# MIXR_Power_-_Battery_Charging.net
KiCad netlist of a schematic drawn in Altium Designer
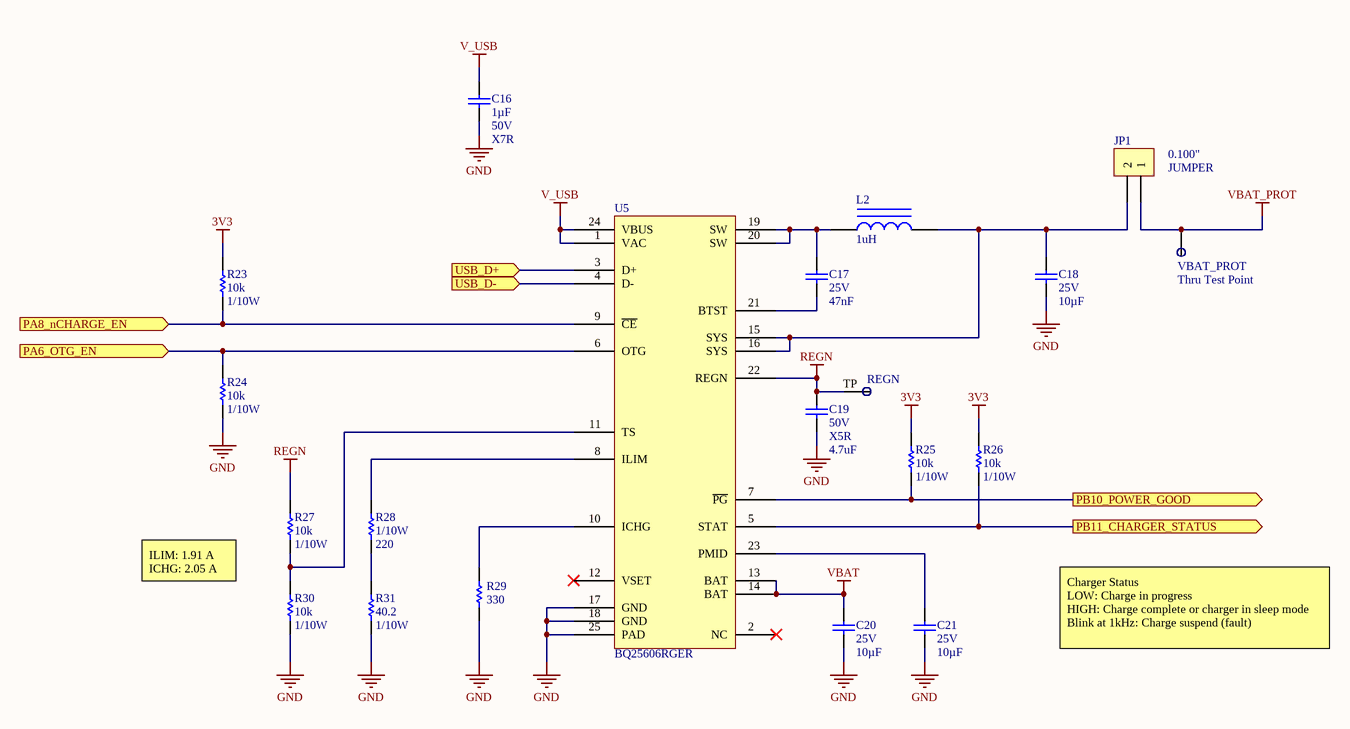
[diagram p0: MIXR Power - Battery Charging.SchDoc]

(export (version "E")
  (design (tool "Eeschema 10.0.6"))
  (components
    (comp (ref "C16")
      (value "CAP CER 1UF 50V 10% X7R 0603")
      (footprint "CAP, 0603")
      (description "1µF ±10% 50V Ceramic Capacitor X7R 0603 (1608 Metric)")
      (fields
        (field (name "TOLERANCE") "±10%")
        (field (name "CAPACITANCE") "1µF")
        (field (name "VOLTAGE") "50V")
        (field (name "TEMPERATURE COEFFICIENT") "X7R")
      )
      (libsource (lib "Schematic Diagrams") (part "CAP CER 1UF 50V 10% X7R 0603"))
    )
    (comp (ref "C17")
      (value "CAP CER 0.047UF 10% 25V X7R 0603")
      (footprint "CAP, 0603")
      (description "0.047µF ±10% 25V Ceramic Capacitor X7R 0603 (1608 Metric)")
      (fields
        (field (name "MANUFACTURER") "KEMET")
        (field (name "TOLERANCE") "10%")
        (field (name "VOLTAGE") "25V")
        (field (name "CAPACITANCE") "47nF")
      )
      (libsource (lib "Schematic Diagrams") (part "CAP CER 0.047UF 10% 25V X7R 0603"))
    )
    (comp (ref "C18")
      (value "CAP CER 10uF 25V 10% X5R 0805")
      (footprint "CAP, 0805")
      (description "10µF ±10% 25V Ceramic Capacitor X5R 0805 (2012 Metric)")
      (fields
        (field (name "MANUFACTURER") "Murata Electronics North America")
        (field (name "MANUFACTURER PART NUMBER") "GRM21BR61E106KA73L")
        (field (name "VOLTAGE - RATED") "25V")
        (field (name "CAPACITANCE") "10µF")
      )
      (libsource (lib "Schematic Diagrams") (part "CAP CER 10uF 25V 10% X5R 0805"))
    )
    (comp (ref "C19")
      (value "4.7uF")
      (footprint "CAP, 0805")
      (description "4.7µF ±20% 50V Ceramic Capacitor X5R 0805 (2012 Metric)")
      (fields
        (field (name "TOLERANCE") "±20%")
        (field (name "VOLTAGE - RATED") "50V")
        (field (name "TEMPERATURE COEFFICIENT") "X5R")
        (field (name "Comment") "CAP CER 4.7UF 50V 10% X5R 0805")
      )
      (libsource (lib "Schematic Diagrams") (part "CAP CER 4.7UF 50V 10% X5R 0805"))
    )
    (comp (ref "C20")
      (value "CAP CER 10uF 25V 10% X5R 0805")
      (footprint "CAP, 0805")
      (description "10µF ±10% 25V Ceramic Capacitor X5R 0805 (2012 Metric)")
      (fields
        (field (name "MANUFACTURER") "Murata Electronics North America")
        (field (name "MANUFACTURER PART NUMBER") "GRM21BR61E106KA73L")
        (field (name "VOLTAGE - RATED") "25V")
        (field (name "CAPACITANCE") "10µF")
      )
      (libsource (lib "Schematic Diagrams") (part "CAP CER 10uF 25V 10% X5R 0805"))
    )
    (comp (ref "C21")
      (value "CAP CER 10uF 25V 10% X5R 0805")
      (footprint "CAP, 0805")
      (description "10µF ±10% 25V Ceramic Capacitor X5R 0805 (2012 Metric)")
      (fields
        (field (name "MANUFACTURER") "Murata Electronics North America")
        (field (name "MANUFACTURER PART NUMBER") "GRM21BR61E106KA73L")
        (field (name "VOLTAGE - RATED") "25V")
        (field (name "CAPACITANCE") "10µF")
      )
      (libsource (lib "Schematic Diagrams") (part "CAP CER 10uF 25V 10% X5R 0805"))
    )
    (comp (ref "JP1")
      (value "JUMPER")
      (footprint "CONN, 2POS JUMPER 0.1\"")
      (description "2 Positions Header Connector Through Hole Gold")
      (fields
        (field (name "MANUFACTURER") "Omron Electronics Inc-EMC Div")
        (field (name "MANUFACTURER PART NUMBER") "XG8T-0231")
        (field (name "ROW SPACING - MATING") "0.100\"")
        (field (name "TYPE") "JUMPER")
      )
      (libsource (lib "Schematic Diagrams") (part "CONN 2POS JUMPER 0.1{dblquote}"))
    )
    (comp (ref "L2")
      (value "IND 1uH 3.8A 25 MOHM SMD")
      (footprint "IND 1uH 3.8A 25 MOHM SMD")
      (description "1µH Shielded Inductor 3.8A 25mOhm Max Nonstandard")
      (fields
        (field (name "MANUFACTURER") "Vishay Dale")
        (field (name "TOLERANCE") "20%")
        (field (name "INDUCTANCE") "1uH")
      )
      (libsource (lib "Schematic Diagrams") (part "IND 1uH 3.8A 25 MOHM SMD"))
    )
    (comp (ref "R23")
      (value "RES 10K OHM 1% 1/10W 0603")
      (footprint "RES, 0603")
      (description "RES SMD 10K OHM 1% 1/10W 0603")
      (fields
        (field (name "TOLERANCE") "±1%")
        (field (name "RESISTANCE") "10k")
        (field (name "POWER") "1/10W")
      )
      (libsource (lib "Schematic Diagrams") (part "RES 10K OHM 1% 1/10W 0603"))
    )
    (comp (ref "R24")
      (value "RES 10K OHM 1% 1/10W 0603")
      (footprint "RES, 0603")
      (description "RES SMD 10K OHM 1% 1/10W 0603")
      (fields
        (field (name "TOLERANCE") "±1%")
        (field (name "RESISTANCE") "10k")
        (field (name "POWER") "1/10W")
      )
      (libsource (lib "Schematic Diagrams") (part "RES 10K OHM 1% 1/10W 0603"))
    )
    (comp (ref "R25")
      (value "RES 10K OHM 1% 1/10W 0603")
      (footprint "RES, 0603")
      (description "RES SMD 10K OHM 1% 1/10W 0603")
      (fields
        (field (name "TOLERANCE") "±1%")
        (field (name "RESISTANCE") "10k")
        (field (name "POWER") "1/10W")
      )
      (libsource (lib "Schematic Diagrams") (part "RES 10K OHM 1% 1/10W 0603"))
    )
    (comp (ref "R26")
      (value "RES 10K OHM 1% 1/10W 0603")
      (footprint "RES, 0603")
      (description "RES SMD 10K OHM 1% 1/10W 0603")
      (fields
        (field (name "TOLERANCE") "±1%")
        (field (name "RESISTANCE") "10k")
        (field (name "POWER") "1/10W")
      )
      (libsource (lib "Schematic Diagrams") (part "RES 10K OHM 1% 1/10W 0603"))
    )
    (comp (ref "R27")
      (value "RES 10K OHM 1% 1/10W 0603")
      (footprint "RES, 0603")
      (description "RES SMD 10K OHM 1% 1/10W 0603")
      (fields
        (field (name "TOLERANCE") "±1%")
        (field (name "RESISTANCE") "10k")
        (field (name "POWER") "1/10W")
      )
      (libsource (lib "Schematic Diagrams") (part "RES 10K OHM 1% 1/10W 0603"))
    )
    (comp (ref "R28")
      (value "RES 220 OHM 1% 1/10W 0603")
      (footprint "RES, 0603")
      (description "220 Ohms ±1% 0.1W, 1/10W Chip Resistor 0603 (1608 Metric) Moisture Resistant Thick Film")
      (fields
        (field (name "MANUFACTURER") "Yageo")
        (field (name "MANUFACTURER PART NUMBER") "RC0603FR-07220RL")
        (field (name "POWER (WATTS)") "1/10W")
        (field (name "RESISTANCE") "220")
      )
      (libsource (lib "Schematic Diagrams") (part "RES 220 OHM 1% 1/10W 0603"))
    )
    (comp (ref "R29")
      (value "330")
      (footprint "RES, 0603")
      (fields
        (field (name "MANUFACTURER") "TE Connectivity")
        (field (name "MANUFACTURER PART NUMBER") "CRGCQ0603F330R")
        (field (name "Comment") "RES 330 OHM 1% 1/10W 0603")
      )
      (libsource (lib "Schematic Diagrams") (part "RES 330 OHM 1% 1/10W 0603"))
    )
    (comp (ref "R30")
      (value "RES 10K OHM 1% 1/10W 0603")
      (footprint "RES, 0603")
      (description "RES SMD 10K OHM 1% 1/10W 0603")
      (fields
        (field (name "TOLERANCE") "±1%")
        (field (name "RESISTANCE") "10k")
        (field (name "POWER") "1/10W")
      )
      (libsource (lib "Schematic Diagrams") (part "RES 10K OHM 1% 1/10W 0603"))
    )
    (comp (ref "R31")
      (value "RES 40.2 OHM 0.5% 1/10W 0603")
      (footprint "RES, 0603")
      (description "RES SMD 40.2 OHM 0.5% 1/10W 0603")
      (fields
        (field (name "TOLERANCE") "±0.5%")
        (field (name "RESISTANCE") "40.2")
        (field (name "POWER") "1/10W")
      )
      (libsource (lib "Schematic Diagrams") (part "RES 40.2 OHM 0.5% 1/10W 0603"))
    )
    (comp (ref "REGN")
      (value "Test Point")
      (footprint "Test Point")
      (libsource (lib "Schematic Diagrams") (part "Test Point"))
    )
    (comp (ref "U5")
      (value "IC BATT CHG LI-ION 1 CELL 24-VQFN")
      (footprint "IC BATT CHG LI-ION 1 CELL 24-VQFN")
      (description "Charger IC Lithium Ion/Polymer 24-VQFN (4x4)")
      (fields
        (field (name "MANUFACTURER") "Texas Instruments")
        (field (name "MANUFACTURER PART NUMBER") "BQ25606RGER")
      )
      (libsource (lib "Schematic Diagrams") (part "IC BATT CHG LI-ION 1 CELL 24-VQFN"))
    )
    (comp (ref "VBAT_PROT")
      (value "Thru Test Point")
      (footprint "Thru Test Point")
      (libsource (lib "Schematic Diagrams") (part "Thru Test Point"))
    )
  )
  (nets
    (net (code "1") (name "/PA6_OTG_EN") (class "Default")
      (node (ref "R24") (pin "1") (pinfunction "1_1") (pintype "passive"))
      (node (ref "U5") (pin "6") (pinfunction "OTG_6") (pintype "passive"))
    )
    (net (code "2") (name "/PA8_nCHARGE_EN") (class "Default")
      (node (ref "R23") (pin "2") (pinfunction "2_2") (pintype "passive"))
      (node (ref "U5") (pin "9") (pinfunction "~{CE}_9") (pintype "passive"))
    )
    (net (code "3") (name "/PB10_POWER_GOOD") (class "Default")
      (node (ref "R25") (pin "2") (pinfunction "2_2") (pintype "passive"))
      (node (ref "U5") (pin "7") (pinfunction "~{PG}_7") (pintype "passive"))
    )
    (net (code "4") (name "/PB11_CHARGER_STATUS") (class "Default")
      (node (ref "R26") (pin "2") (pinfunction "2_2") (pintype "passive"))
      (node (ref "U5") (pin "5") (pinfunction "STAT_5") (pintype "passive"))
    )
    (net (code "5") (name "/USB_D+") (class "Default")
      (node (ref "U5") (pin "3") (pinfunction "D+_3") (pintype "passive"))
    )
    (net (code "6") (name "/USB_D-") (class "Default")
      (node (ref "U5") (pin "4") (pinfunction "D-_4") (pintype "passive"))
    )
    (net (code "7") (name "3V3") (class "Default")
      (node (ref "R23") (pin "1") (pinfunction "1_1") (pintype "passive"))
      (node (ref "R25") (pin "1") (pinfunction "1_1") (pintype "passive"))
      (node (ref "R26") (pin "1") (pinfunction "1_1") (pintype "passive"))
    )
    (net (code "8") (name "GND") (class "Default")
      (node (ref "C16") (pin "2") (pinfunction "2_2") (pintype "passive"))
      (node (ref "C18") (pin "2") (pinfunction "2_2") (pintype "passive"))
      (node (ref "C19") (pin "2") (pinfunction "2_2") (pintype "passive"))
      (node (ref "C20") (pin "2") (pinfunction "2_2") (pintype "passive"))
      (node (ref "C21") (pin "2") (pinfunction "2_2") (pintype "passive"))
      (node (ref "R24") (pin "2") (pinfunction "2_2") (pintype "passive"))
      (node (ref "R29") (pin "2") (pinfunction "2_2") (pintype "passive"))
      (node (ref "R30") (pin "2") (pinfunction "2_2") (pintype "passive"))
      (node (ref "R31") (pin "2") (pinfunction "2_2") (pintype "passive"))
      (node (ref "U5") (pin "17") (pinfunction "GND_17") (pintype "passive"))
      (node (ref "U5") (pin "18") (pinfunction "GND_18") (pintype "passive"))
      (node (ref "U5") (pin "25") (pinfunction "PAD_25") (pintype "passive"))
    )
    (net (code "9") (name "Net-(C17-Pad1)") (class "Default")
      (node (ref "C17") (pin "1") (pinfunction "1_1") (pintype "passive"))
      (node (ref "L2") (pin "1") (pinfunction "1_1") (pintype "passive"))
      (node (ref "U5") (pin "19") (pinfunction "SW_19") (pintype "passive"))
      (node (ref "U5") (pin "20") (pinfunction "SW_20") (pintype "passive"))
    )
    (net (code "10") (name "Net-(C18-Pad1)") (class "Default")
      (node (ref "C18") (pin "1") (pinfunction "1_1") (pintype "passive"))
      (node (ref "JP1") (pin "2") (pinfunction "2_2") (pintype "passive"))
      (node (ref "L2") (pin "2") (pinfunction "2_2") (pintype "passive"))
      (node (ref "U5") (pin "15") (pinfunction "SYS_15") (pintype "passive"))
      (node (ref "U5") (pin "16") (pinfunction "SYS_16") (pintype "passive"))
    )
    (net (code "11") (name "Net-(R28-Pad2)") (class "Default")
      (node (ref "R28") (pin "2") (pinfunction "2_2") (pintype "passive"))
      (node (ref "R31") (pin "1") (pinfunction "1_1") (pintype "passive"))
    )
    (net (code "12") (name "Net-(U5-BTST)") (class "Default")
      (node (ref "C17") (pin "2") (pinfunction "2_2") (pintype "passive"))
      (node (ref "U5") (pin "21") (pinfunction "BTST_21") (pintype "passive"))
    )
    (net (code "13") (name "Net-(U5-ICHG)") (class "Default")
      (node (ref "R29") (pin "1") (pinfunction "1_1") (pintype "passive"))
      (node (ref "U5") (pin "10") (pinfunction "ICHG_10") (pintype "passive"))
    )
    (net (code "14") (name "Net-(U5-ILIM)") (class "Default")
      (node (ref "R28") (pin "1") (pinfunction "1_1") (pintype "passive"))
      (node (ref "U5") (pin "8") (pinfunction "ILIM_8") (pintype "passive"))
    )
    (net (code "15") (name "Net-(U5-PMID)") (class "Default")
      (node (ref "C21") (pin "1") (pinfunction "1_1") (pintype "passive"))
      (node (ref "U5") (pin "23") (pinfunction "PMID_23") (pintype "passive"))
    )
    (net (code "16") (name "Net-(U5-TS)") (class "Default")
      (node (ref "R27") (pin "2") (pinfunction "2_2") (pintype "passive"))
      (node (ref "R30") (pin "1") (pinfunction "1_1") (pintype "passive"))
      (node (ref "U5") (pin "11") (pinfunction "TS_11") (pintype "passive"))
    )
    (net (code "17") (name "REGN") (class "Default")
      (node (ref "C19") (pin "1") (pinfunction "1_1") (pintype "passive"))
      (node (ref "R27") (pin "1") (pinfunction "1_1") (pintype "passive"))
      (node (ref "REGN") (pin "TP") (pinfunction "1_TP") (pintype "passive"))
      (node (ref "U5") (pin "22") (pinfunction "REGN_22") (pintype "passive"))
    )
    (net (code "18") (name "VBAT") (class "Default")
      (node (ref "C20") (pin "1") (pinfunction "1_1") (pintype "passive"))
      (node (ref "U5") (pin "13") (pinfunction "BAT_13") (pintype "passive"))
      (node (ref "U5") (pin "14") (pinfunction "BAT_14") (pintype "passive"))
    )
    (net (code "19") (name "VBAT_PROT") (class "Default")
      (node (ref "JP1") (pin "1") (pinfunction "1_1") (pintype "passive"))
      (node (ref "VBAT_PROT") (pin "TH_TP") (pinfunction "1_TH_TP") (pintype "passive"))
    )
    (net (code "20") (name "V_USB") (class "Default")
      (node (ref "C16") (pin "1") (pinfunction "1_1") (pintype "passive"))
      (node (ref "U5") (pin "1") (pinfunction "VAC_1") (pintype "passive"))
      (node (ref "U5") (pin "24") (pinfunction "VBUS_24") (pintype "passive"))
    )
    (net (code "21") (name "unconnected-(U5-NC-Pad2)") (class "Default")
      (node (ref "U5") (pin "2") (pinfunction "NC_2") (pintype "passive+no_connect"))
    )
    (net (code "22") (name "unconnected-(U5-VSET-Pad12)") (class "Default")
      (node (ref "U5") (pin "12") (pinfunction "VSET_12") (pintype "passive+no_connect"))
    )
  )
)
